# LB_BIT_w16-NAND-v03_1_2.net
KiCad netlist of a schematic drawn in EAGLE
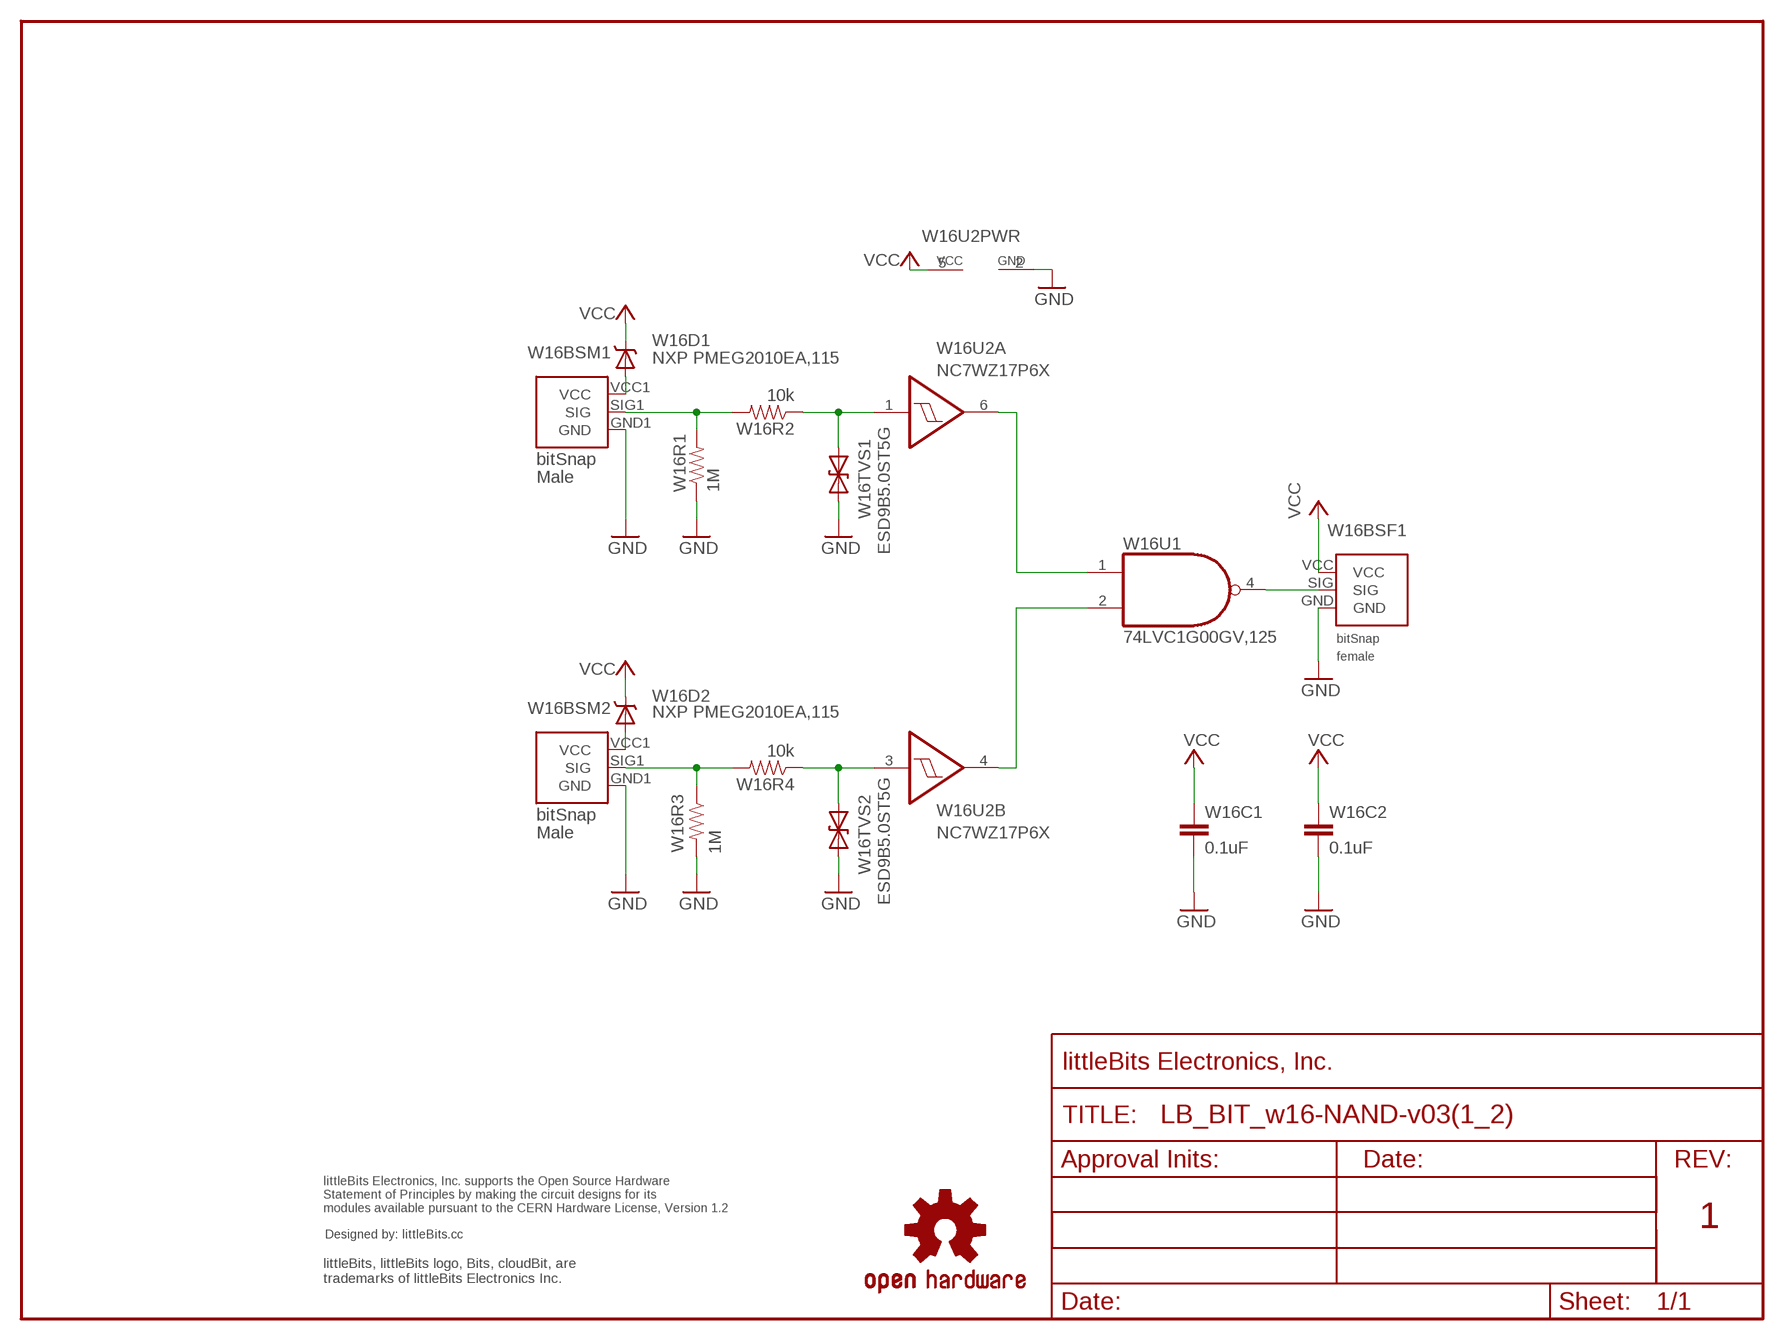
[diagram p0: schematic, sheet 1]

(export (version "E")
  (design (tool "Eeschema 10.0.6"))
  (components
    (comp (ref "U$1")
      (value "OSHWCREDIT")
      (footprint "eagle-import:OSHWCREDIT")
      (libsource (lib "eagle-import") (part "OSHWCREDIT"))
    )
    (comp (ref "U$2")
      (value "OSHW-LOGOL")
      (footprint "eagle-import:OSHW-LOGO-L")
      (libsource (lib "eagle-import") (part "OSHW-LOGOL"))
    )
    (comp (ref "U$7")
      (value "FRAME-LETTER-OHWOHW")
      (footprint "eagle-import:FABDWG01-OHW")
      (libsource (lib "eagle-import") (part "FRAME-LETTER-OHWOHW"))
    )
    (comp (ref "W16BSF1")
      (value "BITSNAP_V03_FEMALE")
      (footprint "eagle-import:BITSNAP_V03_FEMALE")
      (libsource (lib "eagle-import") (part "BITSNAP_V03_FEMALE"))
    )
    (comp (ref "W16BSM1")
      (value "BITSNAP_V03_MALE")
      (footprint "eagle-import:BITSNAP_V03_MALE")
      (libsource (lib "eagle-import") (part "BITSNAP_V03_MALE"))
    )
    (comp (ref "W16BSM2")
      (value "BITSNAP_V03_MALE")
      (footprint "eagle-import:BITSNAP_V03_MALE")
      (libsource (lib "eagle-import") (part "BITSNAP_V03_MALE"))
    )
    (comp (ref "W16C1")
      (value "0.1uF")
      (footprint "eagle-import:CAP-0603")
      (libsource (lib "eagle-import") (part "CAPCAP-0603"))
    )
    (comp (ref "W16C2")
      (value "0.1uF")
      (footprint "eagle-import:CAP-0603")
      (libsource (lib "eagle-import") (part "CAPCAP-0603"))
    )
    (comp (ref "W16D1")
      (value "NXP PMEG2010EA,115")
      (footprint "eagle-import:SOD-323")
      (libsource (lib "eagle-import") (part "DIODE-SCHOTTKY"))
    )
    (comp (ref "W16D2")
      (value "NXP PMEG2010EA,115")
      (footprint "eagle-import:SOD-323")
      (libsource (lib "eagle-import") (part "DIODE-SCHOTTKY"))
    )
    (comp (ref "W16R1")
      (value "1M")
      (footprint "eagle-import:0603-RES")
      (libsource (lib "eagle-import") (part "RESISTOR0603-RES"))
    )
    (comp (ref "W16R2")
      (value "10k")
      (footprint "eagle-import:0603-RES")
      (libsource (lib "eagle-import") (part "RESISTOR0603-RES"))
    )
    (comp (ref "W16R3")
      (value "1M")
      (footprint "eagle-import:0603-RES")
      (libsource (lib "eagle-import") (part "RESISTOR0603-RES"))
    )
    (comp (ref "W16R4")
      (value "10k")
      (footprint "eagle-import:0603-RES")
      (libsource (lib "eagle-import") (part "RESISTOR0603-RES"))
    )
    (comp (ref "W16TVS1")
      (value "ESD9B5.0ST5G")
      (footprint "eagle-import:SOD-923")
      (libsource (lib "eagle-import") (part "DIODE-TVSSOD-923"))
    )
    (comp (ref "W16TVS2")
      (value "ESD9B5.0ST5G")
      (footprint "eagle-import:SOD-923")
      (libsource (lib "eagle-import") (part "DIODE-TVSSOD-923"))
    )
    (comp (ref "W16U1")
      (value "74LVC1G00GV,125")
      (footprint "eagle-import:SOT23-5")
      (libsource (lib "eagle-import") (part "741G00DBVLVC"))
    )
    (comp (ref "W16U2")
      (value "NC7WZ17P6X")
      (footprint "eagle-import:SC70-6")
      (libsource (lib "eagle-import") (part "SCHMITT_TRIGGER_NON_INVERTINGNC7WZ17"))
    )
  )
  (nets
    (net (code "1") (name "GND") (class "Default")
      (node (ref "W16BSF1") (pin "GND") (pinfunction "GND_GND") (pintype "bidirectional"))
      (node (ref "W16BSM1") (pin "GND1") (pinfunction "GND_GND1") (pintype "bidirectional"))
      (node (ref "W16BSM2") (pin "GND1") (pinfunction "GND_GND1") (pintype "bidirectional"))
      (node (ref "W16C1") (pin "2") (pinfunction "2_2") (pintype "passive"))
      (node (ref "W16C2") (pin "2") (pinfunction "2_2") (pintype "passive"))
      (node (ref "W16R1") (pin "1") (pinfunction "1_1") (pintype "passive"))
      (node (ref "W16R3") (pin "2") (pinfunction "2_2") (pintype "passive"))
      (node (ref "W16TVS1") (pin "1") (pinfunction "A_1") (pintype "passive"))
      (node (ref "W16TVS2") (pin "1") (pinfunction "A_1") (pintype "passive"))
      (node (ref "W16U2") (pin "2") (pinfunction "GND_2") (pintype "power_in"))
    )
    (net (code "2") (name "Net-(W16BSM1-SIG)") (class "Default")
      (node (ref "W16BSM1") (pin "SIG1") (pinfunction "SIG_SIG1") (pintype "bidirectional"))
      (node (ref "W16R1") (pin "2") (pinfunction "2_2") (pintype "passive"))
      (node (ref "W16R2") (pin "2") (pinfunction "2_2") (pintype "passive"))
    )
    (net (code "3") (name "Net-(W16BSM1-VCC)") (class "Default")
      (node (ref "W16BSM1") (pin "VCC1") (pinfunction "VCC_VCC1") (pintype "bidirectional"))
      (node (ref "W16D1") (pin "2") (pinfunction "A_2") (pintype "passive"))
    )
    (net (code "4") (name "Net-(W16BSM2-SIG)") (class "Default")
      (node (ref "W16BSM2") (pin "SIG1") (pinfunction "SIG_SIG1") (pintype "bidirectional"))
      (node (ref "W16R3") (pin "1") (pinfunction "1_1") (pintype "passive"))
      (node (ref "W16R4") (pin "2") (pinfunction "2_2") (pintype "passive"))
    )
    (net (code "5") (name "Net-(W16BSM2-VCC)") (class "Default")
      (node (ref "W16BSM2") (pin "VCC1") (pinfunction "VCC_VCC1") (pintype "bidirectional"))
      (node (ref "W16D2") (pin "2") (pinfunction "A_2") (pintype "passive"))
    )
    (net (code "6") (name "Net-(W16TVS1-C)") (class "Default")
      (node (ref "W16R2") (pin "1") (pinfunction "1_1") (pintype "passive"))
      (node (ref "W16TVS1") (pin "2") (pinfunction "C_2") (pintype "passive"))
      (node (ref "W16U2") (pin "1") (pinfunction "I_1") (pintype "input"))
    )
    (net (code "7") (name "Net-(W16TVS2-C)") (class "Default")
      (node (ref "W16R4") (pin "1") (pinfunction "1_1") (pintype "passive"))
      (node (ref "W16TVS2") (pin "2") (pinfunction "C_2") (pintype "passive"))
      (node (ref "W16U2") (pin "3") (pinfunction "I_3") (pintype "input"))
    )
    (net (code "8") (name "Net-(W16U1A-I0)") (class "Default")
      (node (ref "W16U1") (pin "1") (pinfunction "I0_1") (pintype "input"))
      (node (ref "W16U2") (pin "6") (pinfunction "O_6") (pintype "output"))
    )
    (net (code "9") (name "Net-(W16U1A-I1)") (class "Default")
      (node (ref "W16U1") (pin "2") (pinfunction "I1_2") (pintype "input"))
      (node (ref "W16U2") (pin "4") (pinfunction "O_4") (pintype "output"))
    )
    (net (code "10") (name "Net-(W16U1A-O)") (class "Default")
      (node (ref "W16BSF1") (pin "SIG") (pinfunction "SIG_SIG") (pintype "bidirectional"))
      (node (ref "W16U1") (pin "4") (pinfunction "O_4") (pintype "output"))
    )
    (net (code "11") (name "VCC") (class "Default")
      (node (ref "W16BSF1") (pin "VCC") (pinfunction "VCC_VCC") (pintype "bidirectional"))
      (node (ref "W16C1") (pin "1") (pinfunction "1_1") (pintype "passive"))
      (node (ref "W16C2") (pin "1") (pinfunction "1_1") (pintype "passive"))
      (node (ref "W16D1") (pin "1") (pinfunction "C_1") (pintype "passive"))
      (node (ref "W16D2") (pin "1") (pinfunction "C_1") (pintype "passive"))
      (node (ref "W16U2") (pin "5") (pinfunction "VCC_5") (pintype "power_in"))
    )
  )
)
